# midi_buffer.net
KiCad netlist of a schematic drawn in EAGLE
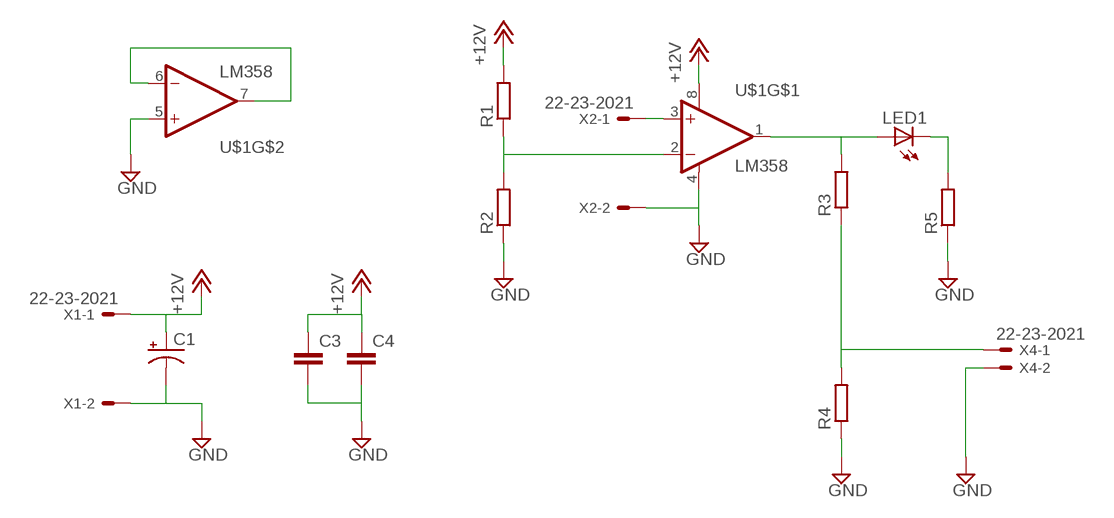
[diagram p0: schematic, sheet 1]

(export (version "E")
  (design (tool "Eeschema 10.0.6"))
  (components
    (comp (ref "C1")
      (value "CPOL-USSMCE")
      (footprint "eagle-import:SMC_E")
      (libsource (lib "eagle-import") (part "CPOL-USSMCE"))
    )
    (comp (ref "C3")
      (value "C-EUC0603K")
      (footprint "eagle-import:C0603K")
      (libsource (lib "eagle-import") (part "C-EUC0603K"))
    )
    (comp (ref "C4")
      (value "C-EUC0603K")
      (footprint "eagle-import:C0603K")
      (libsource (lib "eagle-import") (part "C-EUC0603K"))
    )
    (comp (ref "LED1")
      (value "LEDSML0805")
      (footprint "eagle-import:SML0805")
      (libsource (lib "eagle-import") (part "LEDSML0805"))
    )
    (comp (ref "R1")
      (value "R-EU_R0603")
      (footprint "eagle-import:R0603")
      (libsource (lib "eagle-import") (part "R-EU_R0603"))
    )
    (comp (ref "R2")
      (value "R-EU_R0603")
      (footprint "eagle-import:R0603")
      (libsource (lib "eagle-import") (part "R-EU_R0603"))
    )
    (comp (ref "R3")
      (value "R-EU_R0603")
      (footprint "eagle-import:R0603")
      (libsource (lib "eagle-import") (part "R-EU_R0603"))
    )
    (comp (ref "R4")
      (value "R-EU_R0603")
      (footprint "eagle-import:R0603")
      (libsource (lib "eagle-import") (part "R-EU_R0603"))
    )
    (comp (ref "R5")
      (value "R-EU_R0603")
      (footprint "eagle-import:R0603")
      (libsource (lib "eagle-import") (part "R-EU_R0603"))
    )
    (comp (ref "U$1")
      (value "LM358")
      (footprint "eagle-import:SO08")
      (libsource (lib "eagle-import") (part "LM358"))
    )
    (comp (ref "X1")
      (value "22-23-2021")
      (footprint "eagle-import:22-23-2021")
      (fields (field (name "MF") "MOLEX"))
      (libsource (lib "eagle-import") (part "22-23-2021"))
    )
    (comp (ref "X2")
      (value "22-23-2021")
      (footprint "eagle-import:22-23-2021")
      (fields (field (name "MF") "MOLEX"))
      (libsource (lib "eagle-import") (part "22-23-2021"))
    )
    (comp (ref "X4")
      (value "22-23-2021")
      (footprint "eagle-import:22-23-2021")
      (fields (field (name "MF") "MOLEX"))
      (libsource (lib "eagle-import") (part "22-23-2021"))
    )
  )
  (nets
    (net (code "1") (name "+12V") (class "Default")
      (node (ref "C1") (pin "+") (pinfunction "+_+") (pintype "passive"))
      (node (ref "C3") (pin "1") (pinfunction "1_1") (pintype "passive"))
      (node (ref "C4") (pin "1") (pinfunction "1_1") (pintype "passive"))
      (node (ref "R1") (pin "2") (pinfunction "2_2") (pintype "passive"))
      (node (ref "U$1") (pin "8") (pinfunction "V+_8") (pintype "power_in"))
      (node (ref "X1") (pin "1") (pinfunction "S_1") (pintype "passive"))
    )
    (net (code "2") (name "GND") (class "Default")
      (node (ref "C1") (pin "-") (pinfunction "-_-") (pintype "passive"))
      (node (ref "C3") (pin "2") (pinfunction "2_2") (pintype "passive"))
      (node (ref "C4") (pin "2") (pinfunction "2_2") (pintype "passive"))
      (node (ref "R2") (pin "1") (pinfunction "1_1") (pintype "passive"))
      (node (ref "R4") (pin "1") (pinfunction "1_1") (pintype "passive"))
      (node (ref "R5") (pin "1") (pinfunction "1_1") (pintype "passive"))
      (node (ref "U$1") (pin "4") (pinfunction "V-_4") (pintype "power_in"))
      (node (ref "U$1") (pin "5") (pinfunction "+IN_5") (pintype "input"))
      (node (ref "X1") (pin "2") (pinfunction "S_2") (pintype "passive"))
      (node (ref "X2") (pin "2") (pinfunction "S_2") (pintype "passive"))
      (node (ref "X4") (pin "2") (pinfunction "S_2") (pintype "passive"))
    )
    (net (code "3") (name "Net-(LED1-PadC)") (class "Default")
      (node (ref "LED1") (pin "C") (pinfunction "C_C") (pintype "passive"))
      (node (ref "R5") (pin "2") (pinfunction "2_2") (pintype "passive"))
    )
    (net (code "4") (name "Net-(U$1A-+IN)") (class "Default")
      (node (ref "U$1") (pin "3") (pinfunction "+IN_3") (pintype "input"))
      (node (ref "X2") (pin "1") (pinfunction "S_1") (pintype "passive"))
    )
    (net (code "5") (name "Net-(U$1A--IN)") (class "Default")
      (node (ref "R1") (pin "1") (pinfunction "1_1") (pintype "passive"))
      (node (ref "R2") (pin "2") (pinfunction "2_2") (pintype "passive"))
      (node (ref "U$1") (pin "2") (pinfunction "-IN_2") (pintype "input"))
    )
    (net (code "6") (name "Net-(U$1A-OUT)") (class "Default")
      (node (ref "LED1") (pin "A") (pinfunction "A_A") (pintype "passive"))
      (node (ref "R3") (pin "2") (pinfunction "2_2") (pintype "passive"))
      (node (ref "U$1") (pin "1") (pinfunction "OUT_1") (pintype "output"))
    )
    (net (code "7") (name "Net-(U$1B--IN)") (class "Default")
      (node (ref "U$1") (pin "6") (pinfunction "-IN_6") (pintype "input"))
      (node (ref "U$1") (pin "7") (pinfunction "OUT_7") (pintype "output"))
    )
    (net (code "8") (name "Net-(X4A-S)") (class "Default")
      (node (ref "R3") (pin "1") (pinfunction "1_1") (pintype "passive"))
      (node (ref "R4") (pin "2") (pinfunction "2_2") (pintype "passive"))
      (node (ref "X4") (pin "1") (pinfunction "S_1") (pintype "passive"))
    )
  )
)
